# Sheet1.net
KiCad netlist of a schematic drawn in Altium Designer
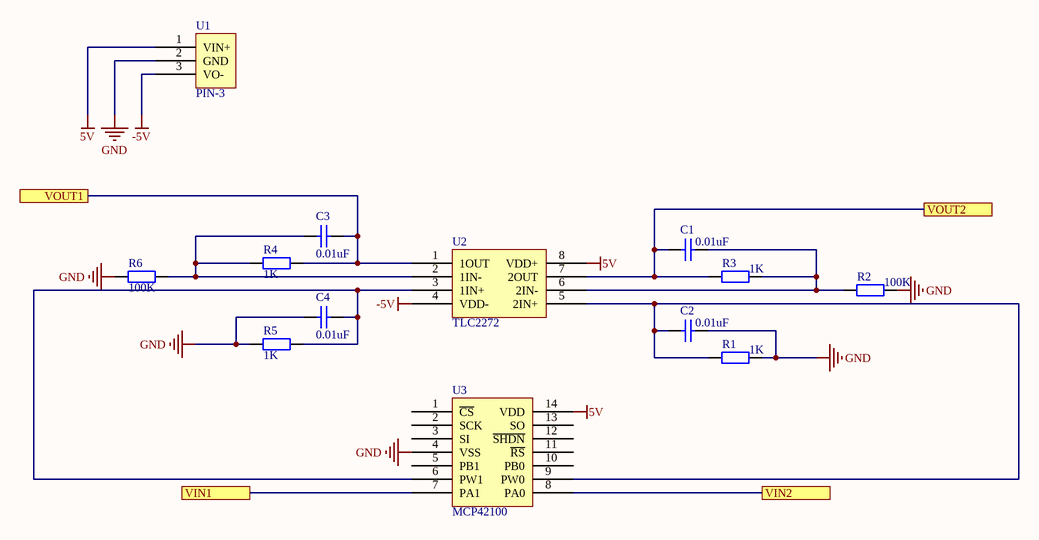
[diagram p0: Sheet1.SchDoc]

(export (version "E")
  (design (tool "Eeschema 10.0.6"))
  (components
    (comp (ref "C1")
      (value "0.01uF")
      (footprint "RAD-0.3")
      (description "Capacitor")
      (fields (field (name "Comment") "Cap") (field (name "PUBLISHER") "Altium Limited"))
      (libsource (lib "Miscellaneous Devices") (part "Cap"))
    )
    (comp (ref "C2")
      (value "0.01uF")
      (footprint "RAD-0.3")
      (description "Capacitor")
      (fields (field (name "Comment") "Cap") (field (name "PUBLISHER") "Altium Limited"))
      (libsource (lib "Miscellaneous Devices") (part "Cap"))
    )
    (comp (ref "C3")
      (value "0.01uF")
      (footprint "RAD-0.3")
      (description "Capacitor")
      (fields (field (name "Comment") "Cap") (field (name "PUBLISHER") "Altium Limited"))
      (libsource (lib "Miscellaneous Devices") (part "Cap"))
    )
    (comp (ref "C4")
      (value "0.01uF")
      (footprint "RAD-0.3")
      (description "Capacitor")
      (fields (field (name "Comment") "Cap") (field (name "PUBLISHER") "Altium Limited"))
      (libsource (lib "Miscellaneous Devices") (part "Cap"))
    )
    (comp (ref "R1")
      (value "1K")
      (footprint "AXIAL-0.4")
      (description "Resistor")
      (fields (field (name "Comment") "Res2") (field (name "PUBLISHER") "Altium Limited"))
      (libsource (lib "") (part "Res2_1"))
    )
    (comp (ref "R2")
      (value "100K")
      (footprint "AXIAL-0.4")
      (description "Resistor")
      (fields (field (name "Comment") "Res2") (field (name "PUBLISHER") "Altium Limited"))
      (libsource (lib "") (part "Res2_1"))
    )
    (comp (ref "R3")
      (value "1K")
      (footprint "AXIAL-0.4")
      (description "Resistor")
      (fields (field (name "Comment") "Res2") (field (name "PUBLISHER") "Altium Limited"))
      (libsource (lib "") (part "Res2_1"))
    )
    (comp (ref "R4")
      (value "1K")
      (footprint "AXIAL-0.4")
      (description "Resistor")
      (fields (field (name "Comment") "Res2") (field (name "PUBLISHER") "Altium Limited"))
      (libsource (lib "Miscellaneous Devices") (part "Res2"))
    )
    (comp (ref "R5")
      (value "1K")
      (footprint "AXIAL-0.4")
      (description "Resistor")
      (fields (field (name "Comment") "Res2") (field (name "PUBLISHER") "Altium Limited"))
      (libsource (lib "Miscellaneous Devices") (part "Res2"))
    )
    (comp (ref "R6")
      (value "100K")
      (footprint "AXIAL-0.4")
      (description "Resistor")
      (fields (field (name "Comment") "Res2") (field (name "PUBLISHER") "Altium Limited"))
      (libsource (lib "Miscellaneous Devices") (part "Res2"))
    )
    (comp (ref "U1") (value "PIN-3") (libsource (lib "TLC2272") (part "PIN-3")))
    (comp (ref "U2") (value "TLC2272") (libsource (lib "TLC2272") (part "TLC2272")))
    (comp (ref "U3") (value "MCP42100") (libsource (lib "MCP42100") (part "MCP42100")))
  )
  (nets
    (net (code "1") (name "-5V") (class "Default")
      (node (ref "U1") (pin "3") (pinfunction "VO-_3") (pintype "passive"))
      (node (ref "U2") (pin "4") (pinfunction "VDD-_4") (pintype "passive"))
    )
    (net (code "2") (name "/VIN1") (class "Default")
      (node (ref "U3") (pin "7") (pinfunction "PA1_7") (pintype "passive"))
    )
    (net (code "3") (name "/VIN2") (class "Default")
      (node (ref "U3") (pin "8") (pinfunction "PA0_8") (pintype "passive"))
    )
    (net (code "4") (name "/VOUT1") (class "Default")
      (node (ref "C3") (pin "1") (pinfunction "1_1") (pintype "passive"))
      (node (ref "R4") (pin "1") (pinfunction "1_1") (pintype "passive"))
      (node (ref "U2") (pin "1") (pinfunction "1OUT_1") (pintype "passive"))
    )
    (net (code "5") (name "/VOUT2") (class "Default")
      (node (ref "C1") (pin "1") (pinfunction "1_1") (pintype "passive"))
      (node (ref "R3") (pin "1") (pinfunction "1_1") (pintype "passive"))
      (node (ref "U2") (pin "7") (pinfunction "2OUT_7") (pintype "passive"))
    )
    (net (code "6") (name "5V") (class "Default")
      (node (ref "U1") (pin "1") (pinfunction "VIN+_1") (pintype "passive"))
      (node (ref "U2") (pin "8") (pinfunction "VDD+_8") (pintype "passive"))
      (node (ref "U3") (pin "14") (pinfunction "VDD_14") (pintype "passive"))
    )
    (net (code "7") (name "GND") (class "Default")
      (node (ref "C2") (pin "2") (pinfunction "2_2") (pintype "passive"))
      (node (ref "C4") (pin "2") (pinfunction "2_2") (pintype "passive"))
      (node (ref "R1") (pin "2") (pinfunction "2_2") (pintype "passive"))
      (node (ref "R2") (pin "2") (pinfunction "2_2") (pintype "passive"))
      (node (ref "R5") (pin "2") (pinfunction "2_2") (pintype "passive"))
      (node (ref "R6") (pin "2") (pinfunction "2_2") (pintype "passive"))
      (node (ref "U1") (pin "2") (pinfunction "GND_2") (pintype "passive"))
      (node (ref "U3") (pin "4") (pinfunction "VSS_4") (pintype "passive"))
    )
    (net (code "8") (name "Net-(U2-1IN+)") (class "Default")
      (node (ref "C4") (pin "1") (pinfunction "1_1") (pintype "passive"))
      (node (ref "R5") (pin "1") (pinfunction "1_1") (pintype "passive"))
      (node (ref "U2") (pin "3") (pinfunction "1IN+_3") (pintype "passive"))
      (node (ref "U3") (pin "6") (pinfunction "PW1_6") (pintype "passive"))
    )
    (net (code "9") (name "Net-(U2-1IN-)") (class "Default")
      (node (ref "C3") (pin "2") (pinfunction "2_2") (pintype "passive"))
      (node (ref "R4") (pin "2") (pinfunction "2_2") (pintype "passive"))
      (node (ref "R6") (pin "1") (pinfunction "1_1") (pintype "passive"))
      (node (ref "U2") (pin "2") (pinfunction "1IN-_2") (pintype "passive"))
    )
    (net (code "10") (name "Net-(U2-2IN+)") (class "Default")
      (node (ref "C2") (pin "1") (pinfunction "1_1") (pintype "passive"))
      (node (ref "R1") (pin "1") (pinfunction "1_1") (pintype "passive"))
      (node (ref "U2") (pin "5") (pinfunction "2IN+_5") (pintype "passive"))
      (node (ref "U3") (pin "9") (pinfunction "PW0_9") (pintype "passive"))
    )
    (net (code "11") (name "Net-(U2-2IN-)") (class "Default")
      (node (ref "C1") (pin "2") (pinfunction "2_2") (pintype "passive"))
      (node (ref "R2") (pin "1") (pinfunction "1_1") (pintype "passive"))
      (node (ref "R3") (pin "2") (pinfunction "2_2") (pintype "passive"))
      (node (ref "U2") (pin "6") (pinfunction "2IN-_6") (pintype "passive"))
    )
    (net (code "12") (name "unconnected-(U3-PB0-Pad10)") (class "Default")
      (node (ref "U3") (pin "10") (pinfunction "PB0_10") (pintype "passive"))
    )
    (net (code "13") (name "unconnected-(U3-PB1-Pad5)") (class "Default")
      (node (ref "U3") (pin "5") (pinfunction "PB1_5") (pintype "passive"))
    )
    (net (code "14") (name "unconnected-(U3-SCK-Pad2)") (class "Default")
      (node (ref "U3") (pin "2") (pinfunction "SCK_2") (pintype "passive"))
    )
    (net (code "15") (name "unconnected-(U3-SI-Pad3)") (class "Default")
      (node (ref "U3") (pin "3") (pinfunction "SI_3") (pintype "passive"))
    )
    (net (code "16") (name "unconnected-(U3-SO-Pad13)") (class "Default")
      (node (ref "U3") (pin "13") (pinfunction "SO_13") (pintype "passive"))
    )
    (net (code "17") (name "unconnected-(U3-~{CS}-Pad1)") (class "Default")
      (node (ref "U3") (pin "1") (pinfunction "~{CS}_1") (pintype "passive"))
    )
    (net (code "18") (name "unconnected-(U3-~{RS}-Pad11)") (class "Default")
      (node (ref "U3") (pin "11") (pinfunction "~{RS}_11") (pintype "passive"))
    )
    (net (code "19") (name "unconnected-(U3-~{SHDN}-Pad12)") (class "Default")
      (node (ref "U3") (pin "12") (pinfunction "~{SHDN}_12") (pintype "passive"))
    )
  )
)
